# serverpowersuply.net
KiCad netlist of a schematic drawn in EasyEDA
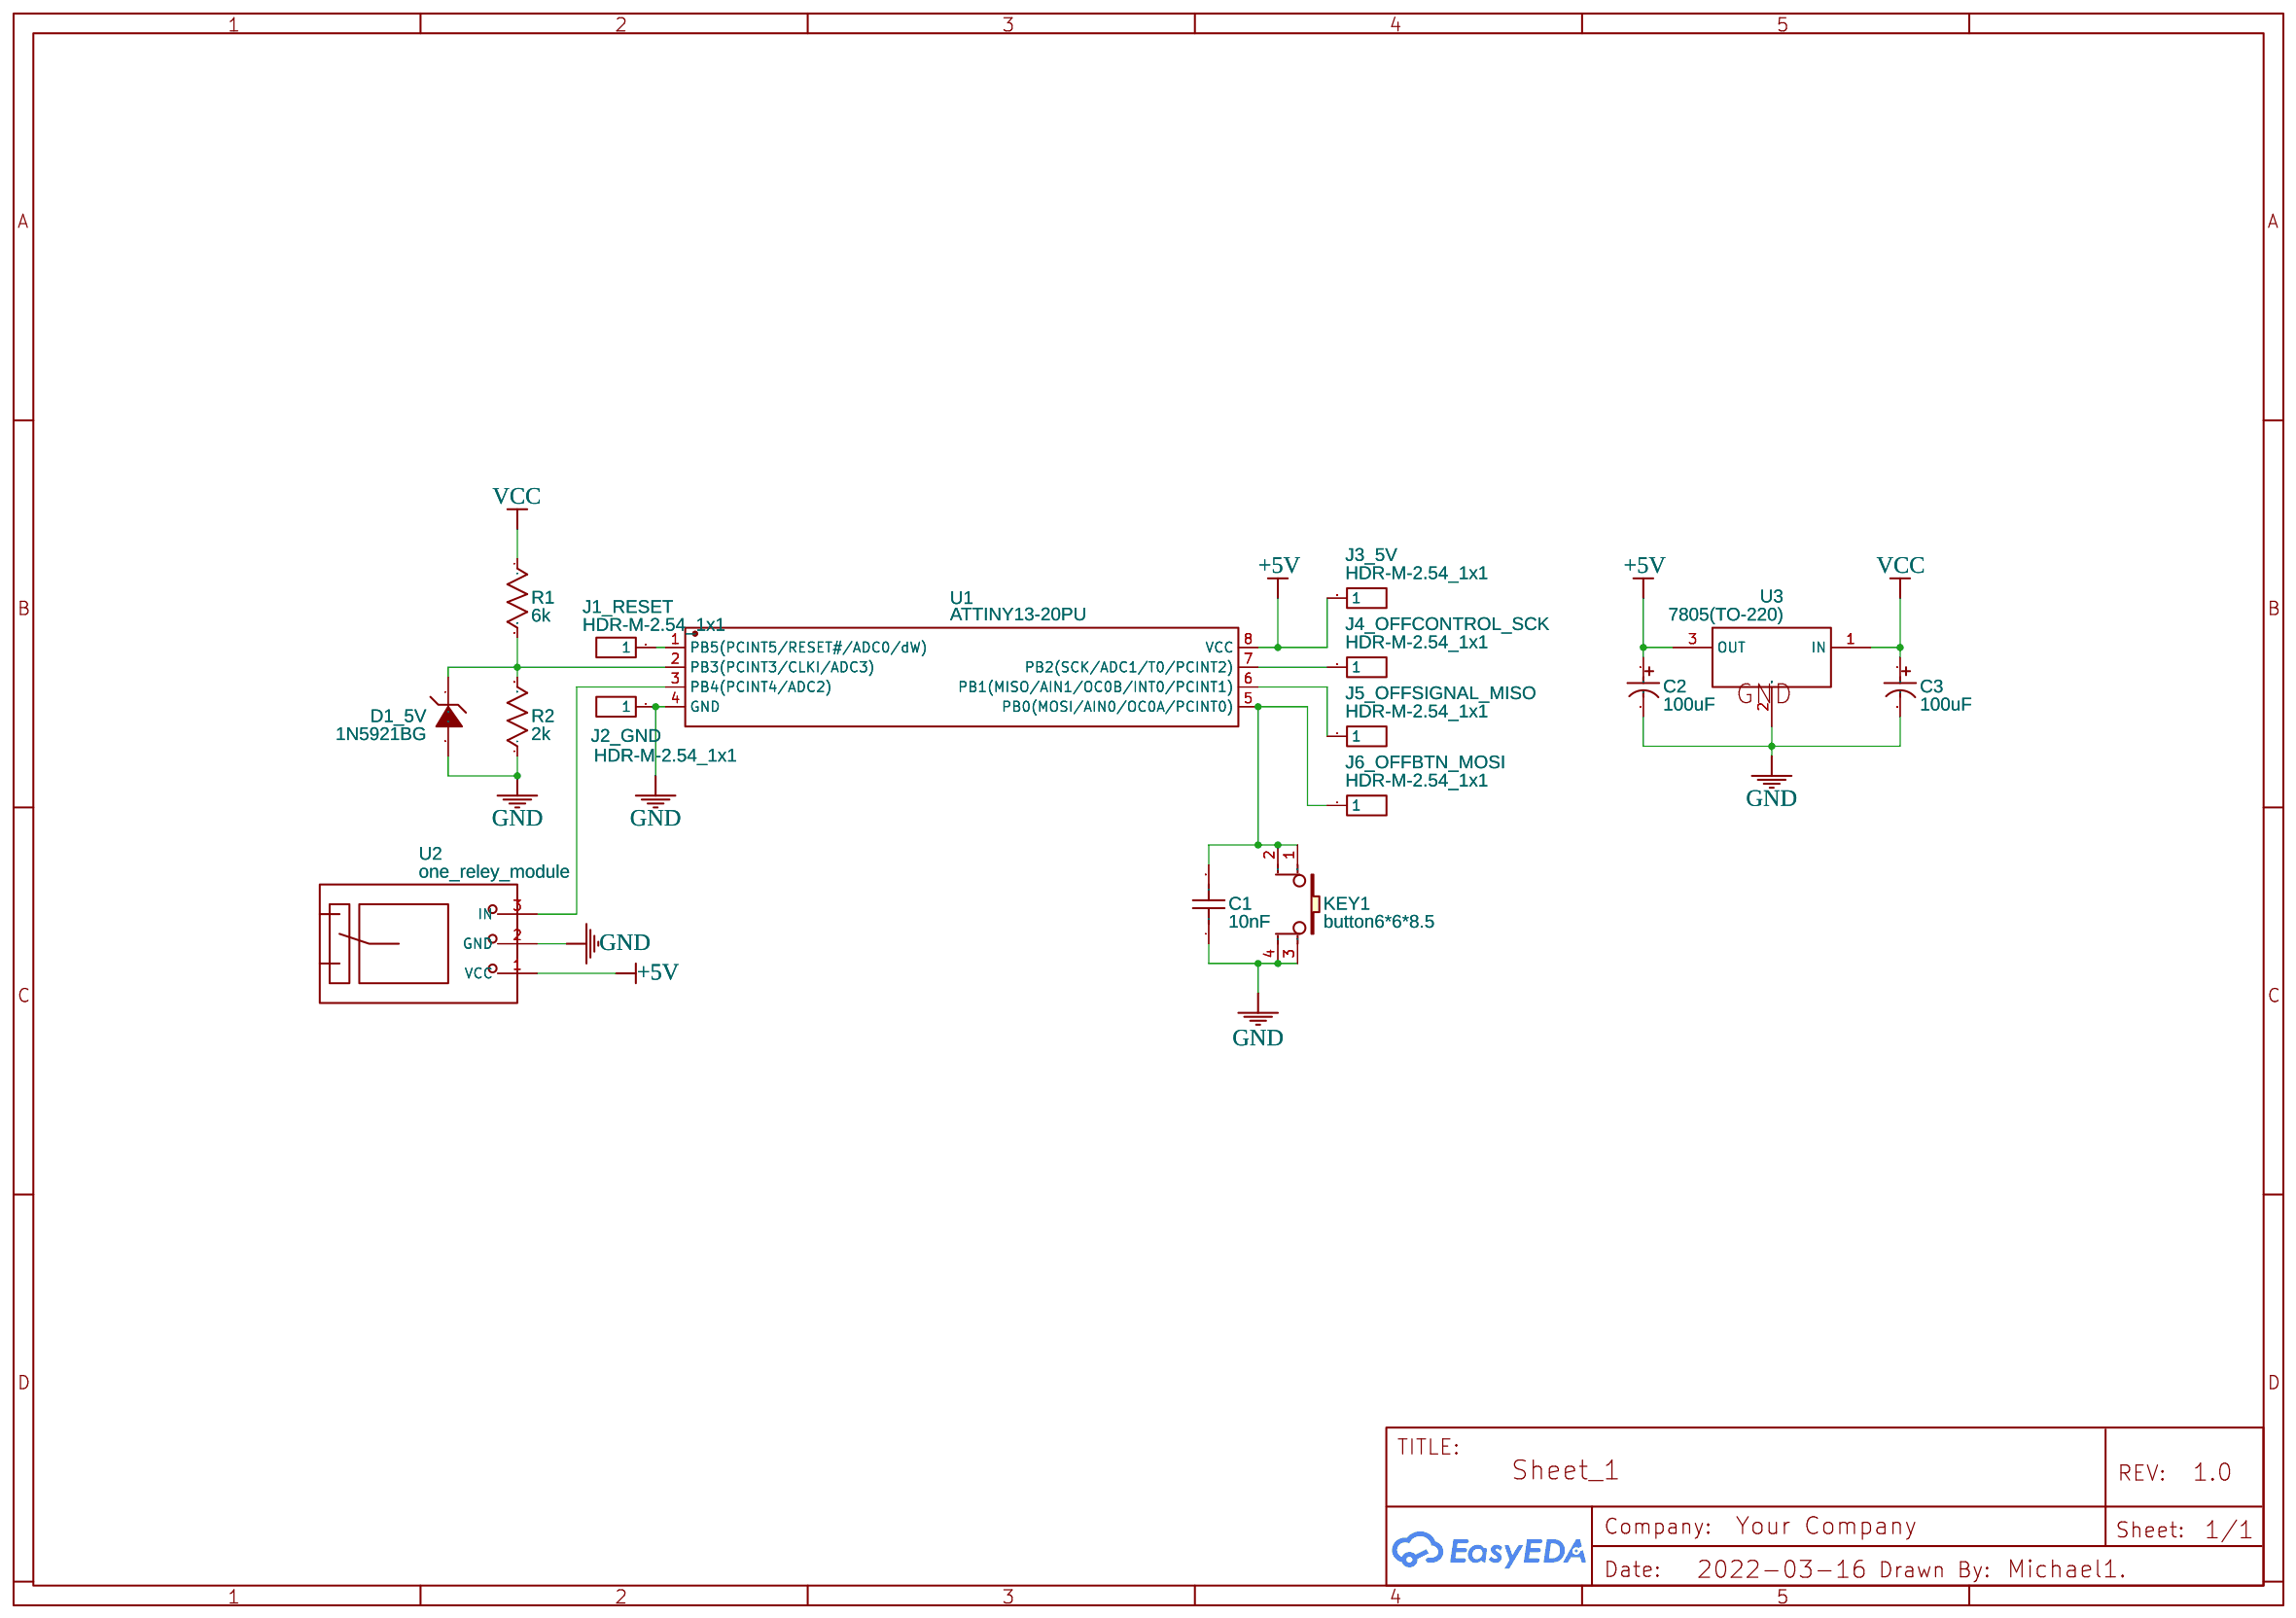
[diagram p0: powerlayout]
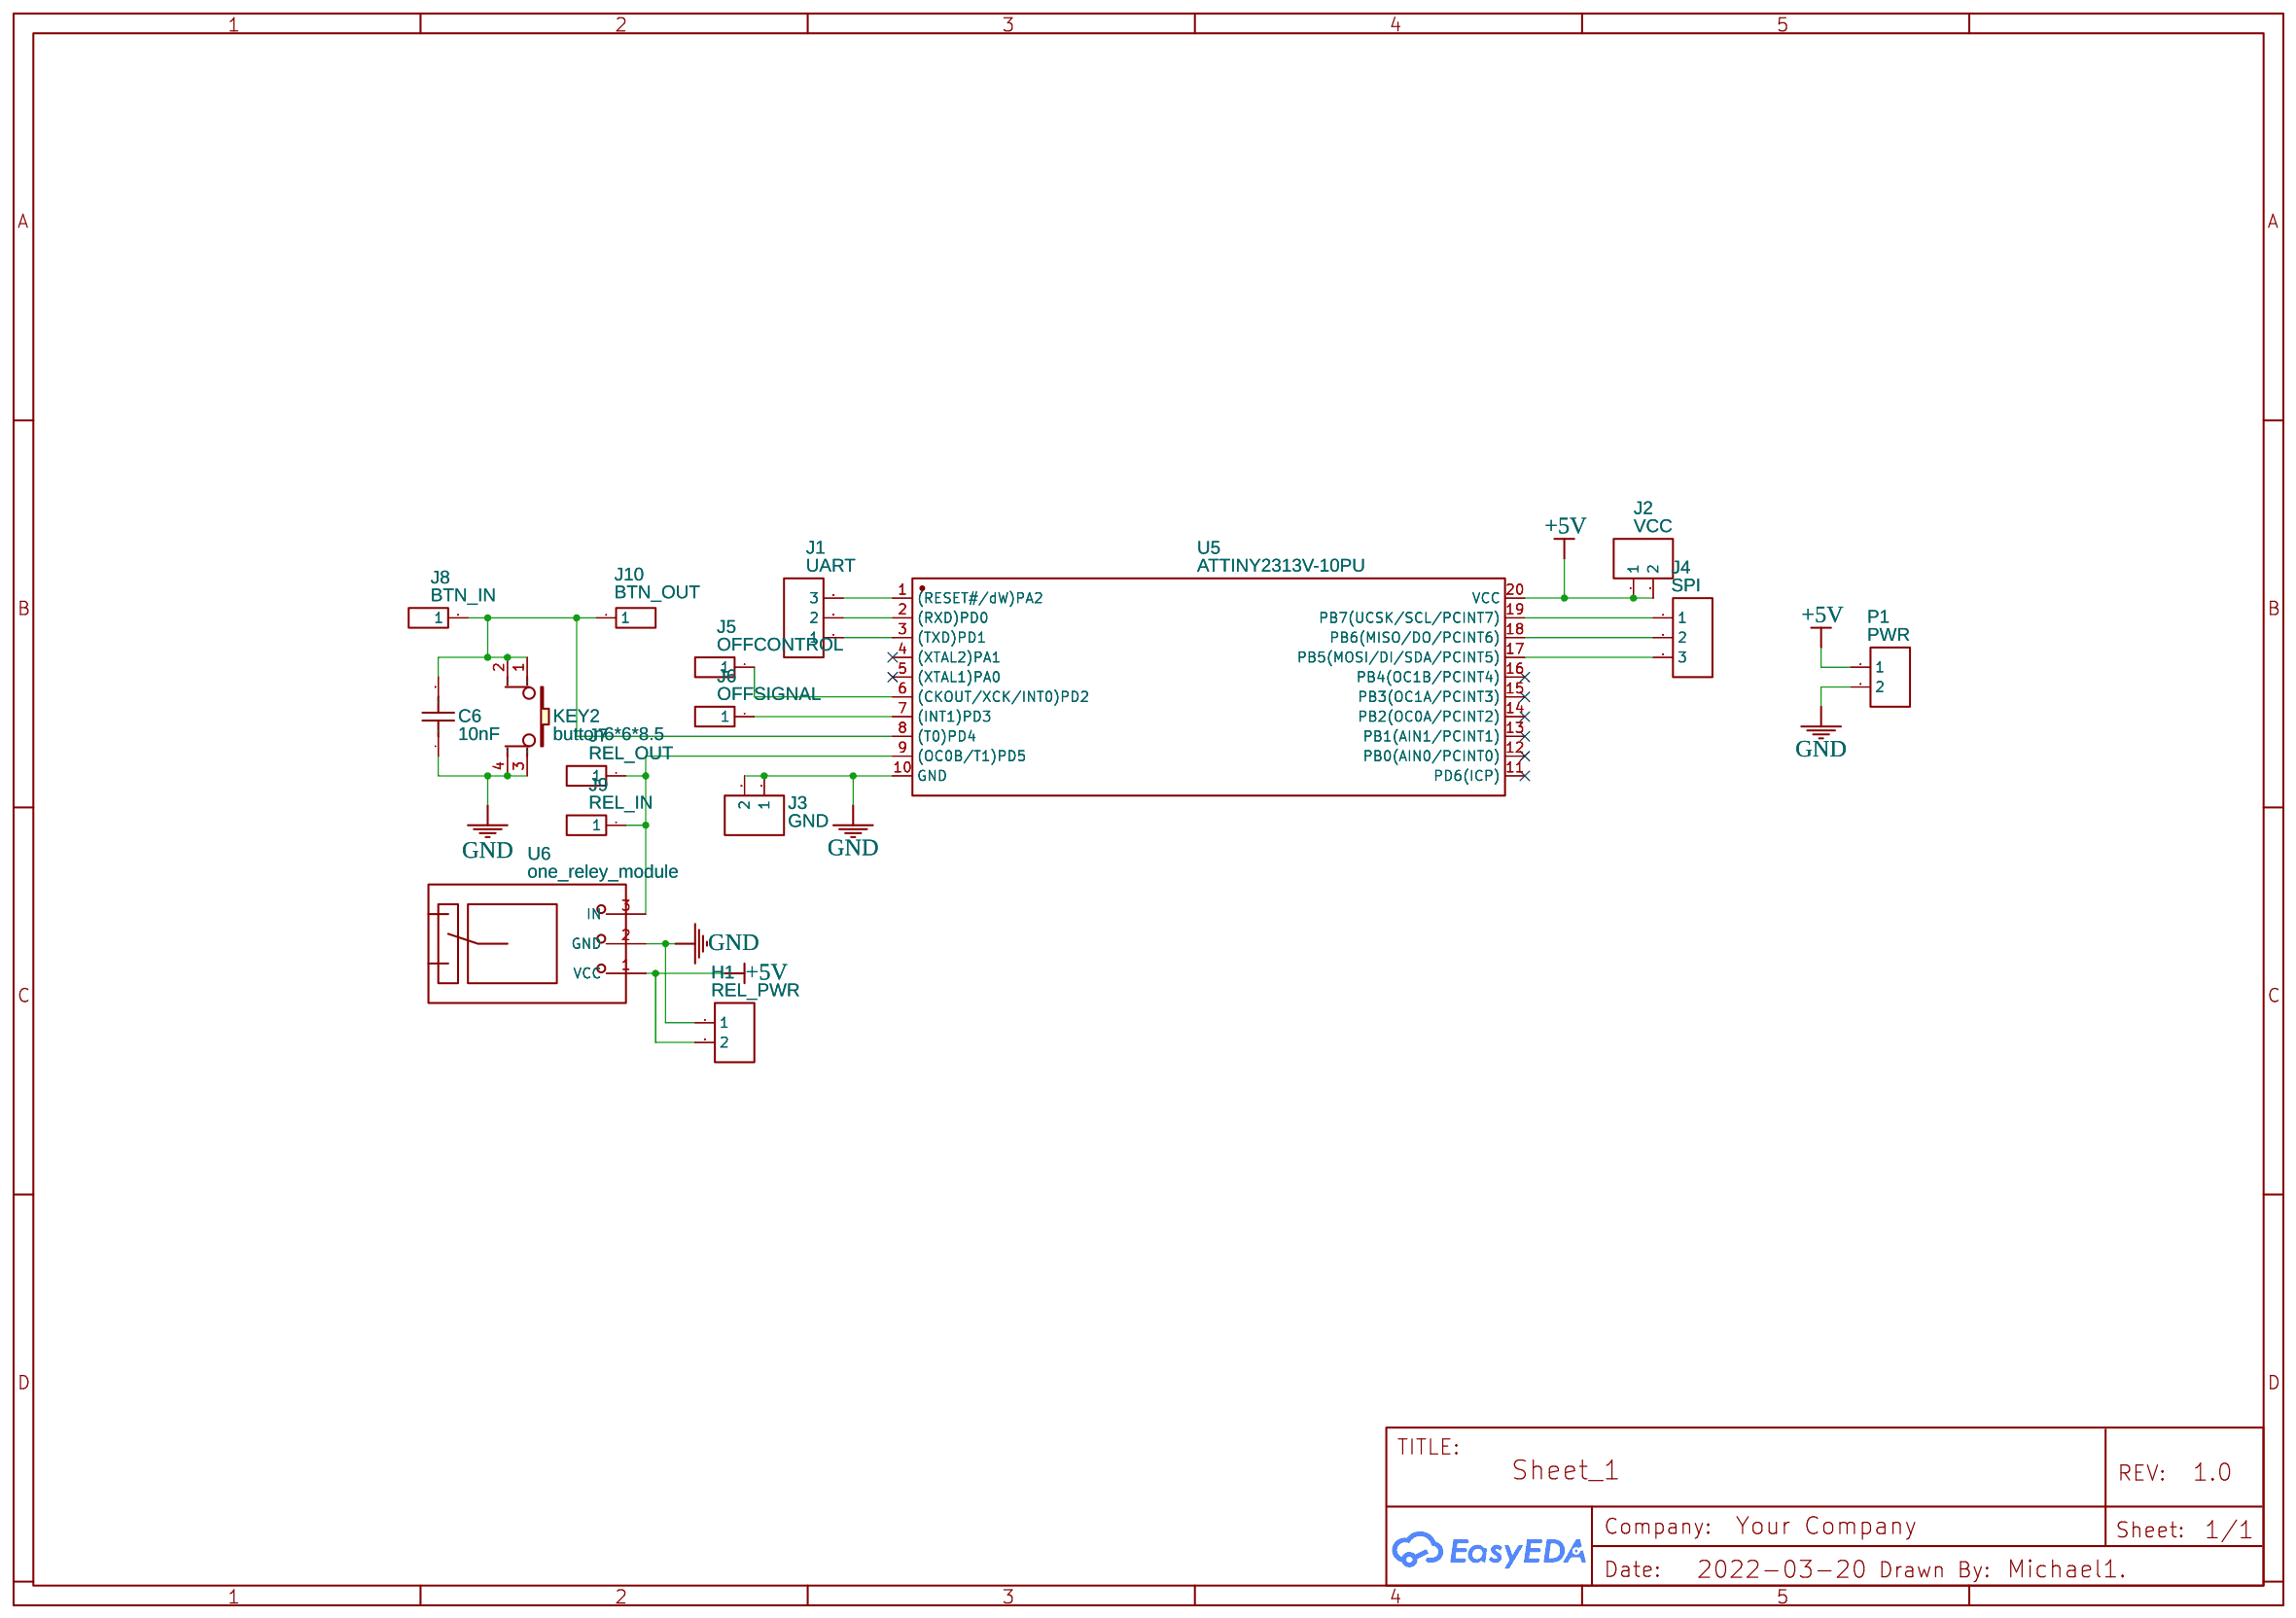
[diagram p1: power2]

(export (version "E")
  (design (tool "Eeschema 10.0.6"))
  (components
    (comp (ref "C1")
      (value "10nF")
      (fields
        (field (name "BOM_Manufacturer Part") "CT4-0805Y103 M500")
        (field (name "BOM_Supplier Part") "C3766")
      )
      (libsource (lib "") (part "CT4-0805Y103 M500"))
    )
    (comp (ref "C2")
      (value "100uF")
      (fields
        (field (name "BOM_Manufacturer Part") "100uF 25V 6.3*7")
        (field (name "BOM_Supplier Part") "C44587")
      )
      (libsource (lib "") (part "100uF 25V 6.3*7"))
    )
    (comp (ref "C3")
      (value "100uF")
      (fields
        (field (name "BOM_Manufacturer Part") "100uF 25V 6.3*7")
        (field (name "BOM_Supplier Part") "C44587")
      )
      (libsource (lib "") (part "100uF 25V 6.3*7"))
    )
    (comp (ref "D1_5V")
      (value "1N5921BG")
      (fields (field (name "BOM_Supplier Part") "C232466"))
      (libsource (lib "") (part "1N5921BG"))
    )
    (comp (ref "J1_RESET")
      (value "HDR-M-2.54_1x1")
      (fields (field (name "BOM_Supplier Part") "C81276"))
      (libsource (lib "") (part "HDR-M-2.54_1x1_5"))
    )
    (comp (ref "J2_GND")
      (value "HDR-M-2.54_1x1")
      (fields (field (name "BOM_Supplier Part") "C81276"))
      (libsource (lib "") (part "HDR-M-2.54_1x1_2"))
    )
    (comp (ref "J3_5V")
      (value "HDR-M-2.54_1x1")
      (fields (field (name "BOM_Supplier Part") "C81276"))
      (libsource (lib "") (part "HDR-M-2.54_1x1_3"))
    )
    (comp (ref "J4_OFFCONTROL_SCK")
      (value "HDR-M-2.54_1x1")
      (fields (field (name "BOM_Supplier Part") "C81276"))
      (libsource (lib "") (part "HDR-M-2.54_1x1_4"))
    )
    (comp (ref "J5_OFFSIGNAL_MISO")
      (value "HDR-M-2.54_1x1")
      (fields (field (name "BOM_Supplier Part") "C81276"))
      (libsource (lib "") (part "HDR-M-2.54_1x1_1"))
    )
    (comp (ref "J6_OFFBTN_MOSI")
      (value "HDR-M-2.54_1x1")
      (fields (field (name "BOM_Supplier Part") "C81276"))
      (libsource (lib "") (part "HDR-M-2.54_1x1"))
    )
    (comp (ref "KEY1")
      (value "button6*6*8.5")
      (fields (field (name "BOM_Supplier Part") "C59980"))
      (libsource (lib "") (part "button6*6*8.5"))
    )
    (comp (ref "R1") (value "6k") (libsource (lib "") (part "R_AXIAL-0.4_US")))
    (comp (ref "R2") (value "2k") (libsource (lib "") (part "R_AXIAL-0.4_US_1")))
    (comp (ref "U1")
      (value "ATTINY13-20PU")
      (fields (field (name "BOM_Supplier Part") "C145757"))
      (libsource (lib "") (part "ATTINY13-20PU"))
    )
    (comp (ref "U2") (value "one_reley_module") (libsource (lib "") (part "one_reley_module")))
    (comp (ref "U3")
      (value "7805(TO-220)")
      (fields (field (name "BOM_Manufacturer Part") "L7805CV-DG") (field (name "BOM_Supplier Part") "C3795"))
      (libsource (lib "") (part "7805(TO-220)"))
    )
    (comp (ref "C6")
      (value "10nF")
      (fields
        (field (name "BOM_Manufacturer Part") "CT4-0805Y103 M500")
        (field (name "BOM_Supplier Part") "C3766")
      )
      (libsource (lib "") (part "CT4-0805Y103 M500"))
    )
    (comp (ref "H1")
      (value "REL_PWR")
      (fields (field (name "BOM_Supplier Part") "C49661"))
      (libsource (lib "") (part "HDR-F-2.54_1x2"))
    )
    (comp (ref "J1")
      (value "UART")
      (fields (field (name "BOM_Supplier Part") "C180248"))
      (libsource (lib "") (part "HDR-M-2.54_1x3"))
    )
    (comp (ref "J2")
      (value "VCC")
      (fields (field (name "BOM_Supplier Part") "C124375"))
      (libsource (lib "") (part "HDR-M-2.54_1x2_1"))
    )
    (comp (ref "J3")
      (value "GND")
      (fields (field (name "BOM_Supplier Part") "C124375"))
      (libsource (lib "") (part "HDR-M-2.54_1x2"))
    )
    (comp (ref "J4")
      (value "SPI")
      (fields (field (name "BOM_Supplier Part") "C180248"))
      (libsource (lib "") (part "HDR-M-2.54_1x3_1"))
    )
    (comp (ref "J5")
      (value "OFFCONTROL")
      (fields (field (name "BOM_Supplier Part") "C81276"))
      (libsource (lib "") (part "HDR-M-2.54_1x1"))
    )
    (comp (ref "J6")
      (value "OFFSIGNAL")
      (fields (field (name "BOM_Supplier Part") "C81276"))
      (libsource (lib "") (part "HDR-M-2.54_1x1"))
    )
    (comp (ref "J7")
      (value "REL_OUT")
      (fields (field (name "BOM_Supplier Part") "C81276"))
      (libsource (lib "") (part "HDR-M-2.54_1x1"))
    )
    (comp (ref "J8")
      (value "BTN_IN")
      (fields (field (name "BOM_Supplier Part") "C81276"))
      (libsource (lib "") (part "HDR-M-2.54_1x1"))
    )
    (comp (ref "J9")
      (value "REL_IN")
      (fields (field (name "BOM_Supplier Part") "C81276"))
      (libsource (lib "") (part "HDR-M-2.54_1x1"))
    )
    (comp (ref "J10")
      (value "BTN_OUT")
      (fields (field (name "BOM_Supplier Part") "C81276"))
      (libsource (lib "") (part "HDR-M-2.54_1x1_1"))
    )
    (comp (ref "KEY2")
      (value "button6*6*8.5")
      (fields (field (name "BOM_Supplier Part") "C59980"))
      (libsource (lib "") (part "button6*6*8.5"))
    )
    (comp (ref "P1") (value "PWR") (libsource (lib "") (part "CONN-TH_2P-P5.00")))
    (comp (ref "U5")
      (value "ATTINY2313V-10PU")
      (fields (field (name "BOM_Supplier Part") "C613485"))
      (libsource (lib "") (part "ATTINY2313V-10PU"))
    )
    (comp (ref "U6") (value "one_reley_module") (libsource (lib "") (part "one_reley_module")))
  )
  (nets
    (net (code "1") (name "+5V") (class "Default")
      (node (ref "C2") (pin "1") (pinfunction "1_1") (pintype "input"))
      (node (ref "H1") (pin "2") (pinfunction "2_2") (pintype "input"))
      (node (ref "J2") (pin "1") (pinfunction "1_1") (pintype "unspecified"))
      (node (ref "J2") (pin "2") (pinfunction "2_2") (pintype "unspecified"))
      (node (ref "J3_5V") (pin "1") (pinfunction "1_1") (pintype "input"))
      (node (ref "P1") (pin "1") (pinfunction "1_1") (pintype "unspecified"))
      (node (ref "U1") (pin "8") (pinfunction "VCC_8") (pintype "unspecified"))
      (node (ref "U2") (pin "1") (pinfunction "VCC_1") (pintype "unspecified"))
      (node (ref "U3") (pin "3") (pinfunction "OUT_3") (pintype "passive"))
      (node (ref "U5") (pin "20") (pinfunction "VCC_20") (pintype "unspecified"))
      (node (ref "U6") (pin "1") (pinfunction "VCC_1") (pintype "unspecified"))
    )
    (net (code "2") (name "GND") (class "Default")
      (node (ref "C1") (pin "1") (pinfunction "1_1") (pintype "unspecified"))
      (node (ref "C2") (pin "2") (pinfunction "2_2") (pintype "input"))
      (node (ref "C3") (pin "2") (pinfunction "2_2") (pintype "input"))
      (node (ref "C6") (pin "1") (pinfunction "1_1") (pintype "unspecified"))
      (node (ref "D1_5V") (pin "2") (pinfunction "A_2") (pintype "unspecified"))
      (node (ref "H1") (pin "1") (pinfunction "1_1") (pintype "input"))
      (node (ref "J2_GND") (pin "1") (pinfunction "1_1") (pintype "input"))
      (node (ref "J3") (pin "1") (pinfunction "1_1") (pintype "unspecified"))
      (node (ref "J3") (pin "2") (pinfunction "2_2") (pintype "unspecified"))
      (node (ref "KEY1") (pin "3") (pinfunction "3_3") (pintype "input"))
      (node (ref "KEY1") (pin "4") (pinfunction "4_4") (pintype "input"))
      (node (ref "KEY2") (pin "3") (pinfunction "3_3") (pintype "input"))
      (node (ref "KEY2") (pin "4") (pinfunction "4_4") (pintype "input"))
      (node (ref "P1") (pin "2") (pinfunction "2_2") (pintype "unspecified"))
      (node (ref "R2") (pin "1") (pinfunction "1_1") (pintype "unspecified"))
      (node (ref "U1") (pin "4") (pinfunction "GND_4") (pintype "unspecified"))
      (node (ref "U2") (pin "2") (pinfunction "GND_2") (pintype "unspecified"))
      (node (ref "U3") (pin "2") (pinfunction "GND_2") (pintype "passive"))
      (node (ref "U5") (pin "10") (pinfunction "GND_10") (pintype "unspecified"))
      (node (ref "U6") (pin "2") (pinfunction "GND_2") (pintype "unspecified"))
    )
    (net (code "3") (name "Net-(D1_5V-C)") (class "Default")
      (node (ref "D1_5V") (pin "1") (pinfunction "C_1") (pintype "unspecified"))
      (node (ref "R1") (pin "2") (pinfunction "2_2") (pintype "unspecified"))
      (node (ref "R2") (pin "2") (pinfunction "2_2") (pintype "unspecified"))
      (node (ref "U1") (pin "2") (pinfunction "PB3(PCINT3/CLKI/ADC3)_2") (pintype "unspecified"))
    )
    (net (code "4") (name "Net-(U1-PB0(MOSI{slash}AIN0{slash}OC0A{slash}PCINT0))") (class "Default")
      (node (ref "C1") (pin "2") (pinfunction "2_2") (pintype "unspecified"))
      (node (ref "J6_OFFBTN_MOSI") (pin "1") (pinfunction "1_1") (pintype "input"))
      (node (ref "KEY1") (pin "1") (pinfunction "1_1") (pintype "input"))
      (node (ref "KEY1") (pin "2") (pinfunction "2_2") (pintype "input"))
      (node (ref "U1") (pin "5") (pinfunction "PB0(MOSI/AIN0/OC0A/PCINT0)_5") (pintype "unspecified"))
    )
    (net (code "5") (name "Net-(U1-PB1(MISO{slash}AIN1{slash}OC0B{slash}INT0{slash}PCINT1))") (class "Default")
      (node (ref "J5_OFFSIGNAL_MISO") (pin "1") (pinfunction "1_1") (pintype "input"))
      (node (ref "U1") (pin "6") (pinfunction "PB1(MISO/AIN1/OC0B/INT0/PCINT1)_6") (pintype "unspecified"))
    )
    (net (code "6") (name "Net-(U1-PB2(SCK{slash}ADC1{slash}T0{slash}PCINT2))") (class "Default")
      (node (ref "J4_OFFCONTROL_SCK") (pin "1") (pinfunction "1_1") (pintype "input"))
      (node (ref "U1") (pin "7") (pinfunction "PB2(SCK/ADC1/T0/PCINT2)_7") (pintype "unspecified"))
    )
    (net (code "7") (name "Net-(U1-PB4(PCINT4{slash}ADC2))") (class "Default")
      (node (ref "U1") (pin "3") (pinfunction "PB4(PCINT4/ADC2)_3") (pintype "unspecified"))
      (node (ref "U2") (pin "3") (pinfunction "IN_3") (pintype "unspecified"))
    )
    (net (code "8") (name "Net-(U1-PB5(PCINT5{slash}RESET#{slash}ADC0{slash}dW))") (class "Default")
      (node (ref "J1_RESET") (pin "1") (pinfunction "1_1") (pintype "input"))
      (node (ref "U1") (pin "1") (pinfunction "PB5(PCINT5/RESET#/ADC0/dW)_1") (pintype "unspecified"))
    )
    (net (code "9") (name "Net-(U5-(CKOUT{slash}XCK{slash}INT0)PD2)") (class "Default")
      (node (ref "J5") (pin "1") (pinfunction "1_1") (pintype "input"))
      (node (ref "U5") (pin "6") (pinfunction "(CKOUT/XCK/INT0)PD2_6") (pintype "unspecified"))
    )
    (net (code "10") (name "Net-(U5-(INT1)PD3)") (class "Default")
      (node (ref "J6") (pin "1") (pinfunction "1_1") (pintype "input"))
      (node (ref "U5") (pin "7") (pinfunction "(INT1)PD3_7") (pintype "unspecified"))
    )
    (net (code "11") (name "Net-(U5-(OC0B{slash}T1)PD5)") (class "Default")
      (node (ref "J7") (pin "1") (pinfunction "1_1") (pintype "input"))
      (node (ref "J9") (pin "1") (pinfunction "1_1") (pintype "input"))
      (node (ref "U5") (pin "9") (pinfunction "(OC0B/T1)PD5_9") (pintype "unspecified"))
      (node (ref "U6") (pin "3") (pinfunction "IN_3") (pintype "unspecified"))
    )
    (net (code "12") (name "Net-(U5-(RESET#{slash}dW)PA2)") (class "Default")
      (node (ref "J1") (pin "3") (pinfunction "3_3") (pintype "input"))
      (node (ref "U5") (pin "1") (pinfunction "(RESET#/dW)PA2_1") (pintype "unspecified"))
    )
    (net (code "13") (name "Net-(U5-(RXD)PD0)") (class "Default")
      (node (ref "J1") (pin "2") (pinfunction "2_2") (pintype "input"))
      (node (ref "U5") (pin "2") (pinfunction "(RXD)PD0_2") (pintype "unspecified"))
    )
    (net (code "14") (name "Net-(U5-(T0)PD4)") (class "Default")
      (node (ref "C6") (pin "2") (pinfunction "2_2") (pintype "unspecified"))
      (node (ref "J10") (pin "1") (pinfunction "1_1") (pintype "input"))
      (node (ref "J8") (pin "1") (pinfunction "1_1") (pintype "input"))
      (node (ref "KEY2") (pin "1") (pinfunction "1_1") (pintype "input"))
      (node (ref "KEY2") (pin "2") (pinfunction "2_2") (pintype "input"))
      (node (ref "U5") (pin "8") (pinfunction "(T0)PD4_8") (pintype "unspecified"))
    )
    (net (code "15") (name "Net-(U5-(TXD)PD1)") (class "Default")
      (node (ref "J1") (pin "1") (pinfunction "1_1") (pintype "input"))
      (node (ref "U5") (pin "3") (pinfunction "(TXD)PD1_3") (pintype "unspecified"))
    )
    (net (code "16") (name "Net-(U5-PB5(MOSI{slash}DI{slash}SDA{slash}PCINT5))") (class "Default")
      (node (ref "J4") (pin "3") (pinfunction "3_3") (pintype "input"))
      (node (ref "U5") (pin "17") (pinfunction "PB5(MOSI/DI/SDA/PCINT5)_17") (pintype "unspecified"))
    )
    (net (code "17") (name "Net-(U5-PB6(MISO{slash}DO{slash}PCINT6))") (class "Default")
      (node (ref "J4") (pin "2") (pinfunction "2_2") (pintype "input"))
      (node (ref "U5") (pin "18") (pinfunction "PB6(MISO/DO/PCINT6)_18") (pintype "unspecified"))
    )
    (net (code "18") (name "Net-(U5-PB7(UCSK{slash}SCL{slash}PCINT7))") (class "Default")
      (node (ref "J4") (pin "1") (pinfunction "1_1") (pintype "input"))
      (node (ref "U5") (pin "19") (pinfunction "PB7(UCSK/SCL/PCINT7)_19") (pintype "unspecified"))
    )
    (net (code "19") (name "VCC") (class "Default")
      (node (ref "C3") (pin "1") (pinfunction "1_1") (pintype "input"))
      (node (ref "R1") (pin "1") (pinfunction "1_1") (pintype "unspecified"))
      (node (ref "U3") (pin "1") (pinfunction "IN_1") (pintype "passive"))
    )
    (net (code "20") (name "unconnected-(U5-(XTAL1)PA0-Pad5)") (class "Default")
      (node (ref "U5") (pin "5") (pinfunction "(XTAL1)PA0_5") (pintype "unspecified+no_connect"))
    )
    (net (code "21") (name "unconnected-(U5-(XTAL2)PA1-Pad4)") (class "Default")
      (node (ref "U5") (pin "4") (pinfunction "(XTAL2)PA1_4") (pintype "unspecified+no_connect"))
    )
    (net (code "22") (name "unconnected-(U5-PB0(AIN0{slash}PCINT0)-Pad12)") (class "Default")
      (node (ref "U5") (pin "12") (pinfunction "PB0(AIN0/PCINT0)_12") (pintype "unspecified+no_connect"))
    )
    (net (code "23") (name "unconnected-(U5-PB1(AIN1{slash}PCINT1)-Pad13)") (class "Default")
      (node (ref "U5") (pin "13") (pinfunction "PB1(AIN1/PCINT1)_13") (pintype "unspecified+no_connect"))
    )
    (net (code "24") (name "unconnected-(U5-PB2(OC0A{slash}PCINT2)-Pad14)") (class "Default")
      (node (ref "U5") (pin "14") (pinfunction "PB2(OC0A/PCINT2)_14") (pintype "unspecified+no_connect"))
    )
    (net (code "25") (name "unconnected-(U5-PB3(OC1A{slash}PCINT3)-Pad15)") (class "Default")
      (node (ref "U5") (pin "15") (pinfunction "PB3(OC1A/PCINT3)_15") (pintype "unspecified+no_connect"))
    )
    (net (code "26") (name "unconnected-(U5-PB4(OC1B{slash}PCINT4)-Pad16)") (class "Default")
      (node (ref "U5") (pin "16") (pinfunction "PB4(OC1B/PCINT4)_16") (pintype "unspecified+no_connect"))
    )
    (net (code "27") (name "unconnected-(U5-PD6(ICP)-Pad11)") (class "Default")
      (node (ref "U5") (pin "11") (pinfunction "PD6(ICP)_11") (pintype "unspecified+no_connect"))
    )
  )
)
